# mp_rollerball.net
KiCad netlist of a schematic drawn in EAGLE
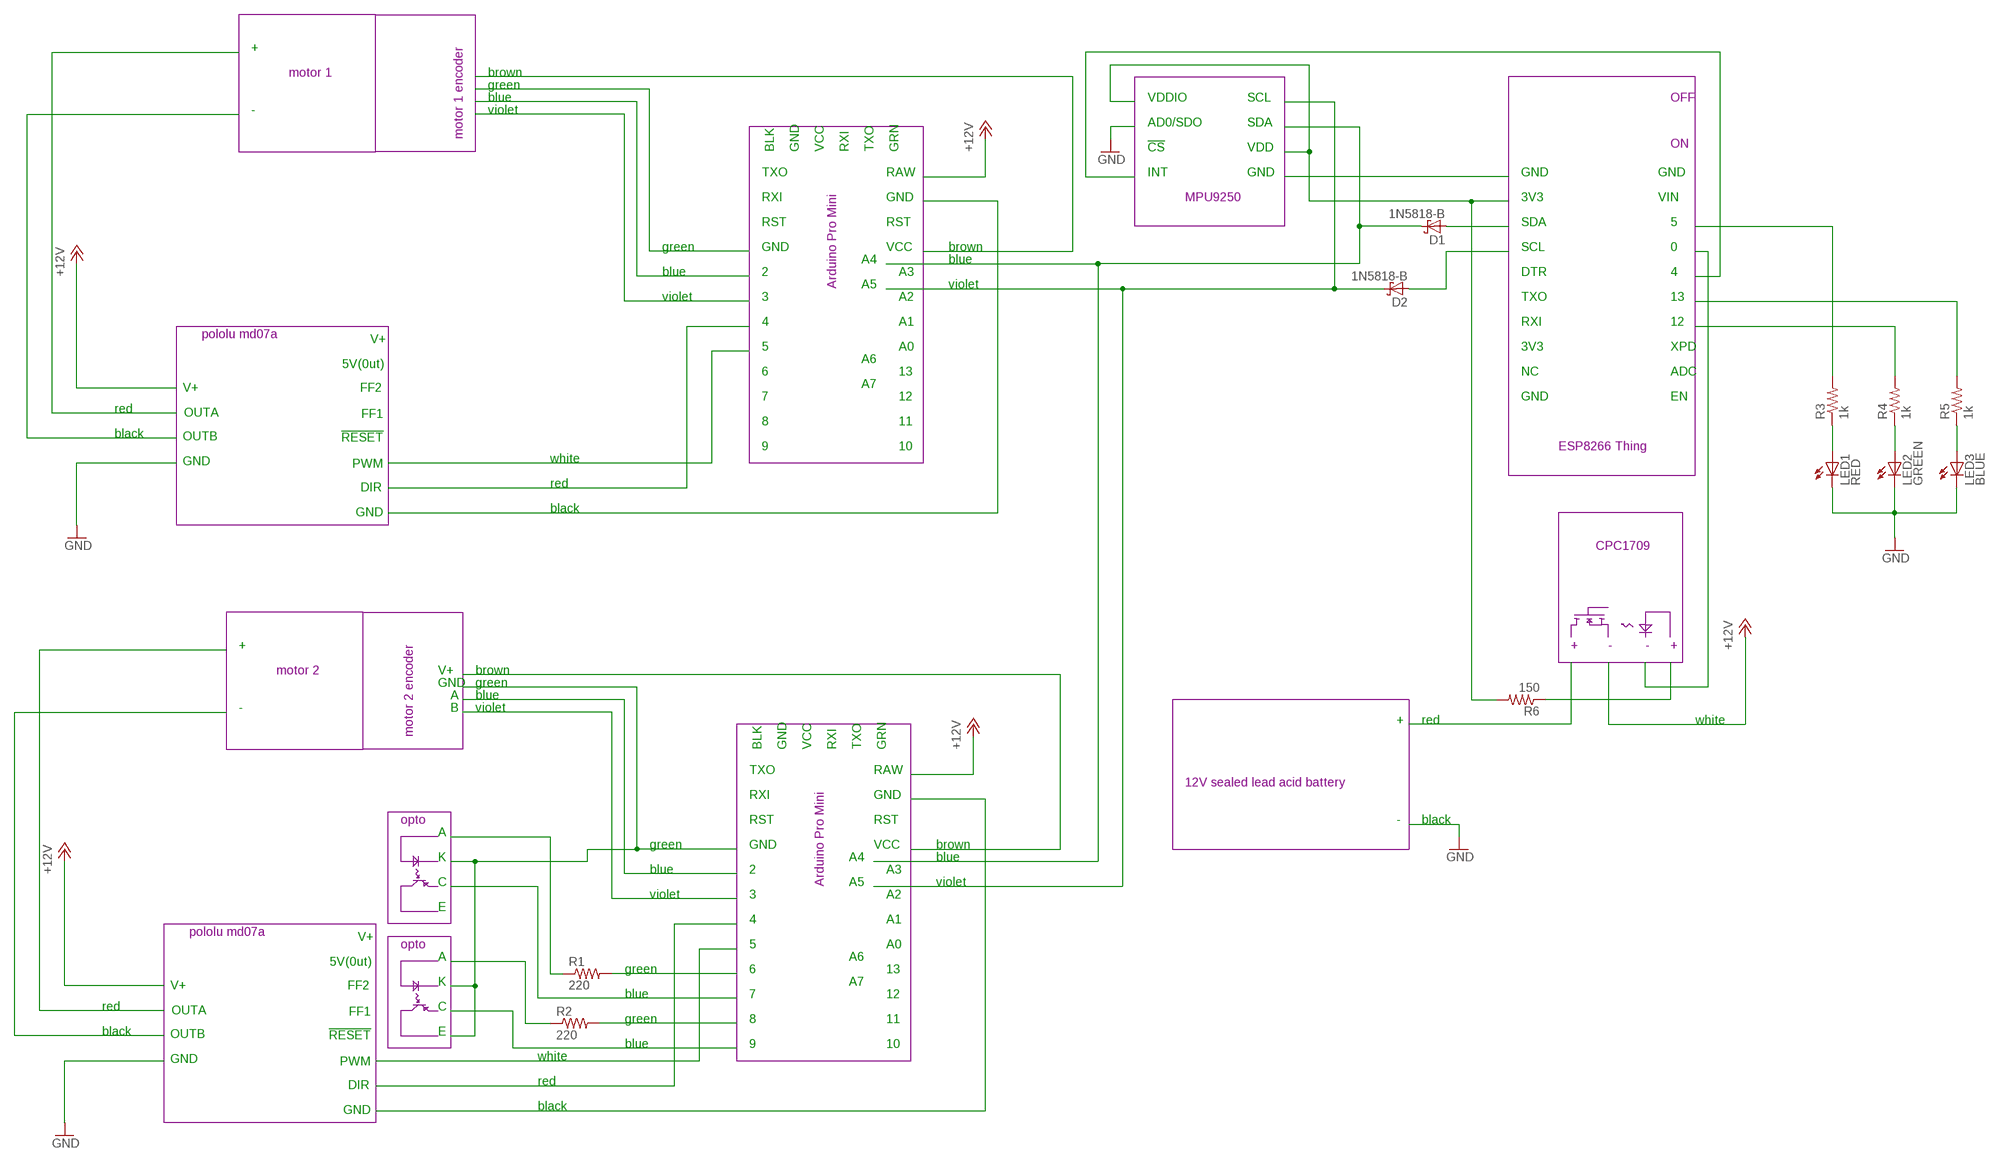
[diagram p0: schematic, sheet 1]

(export (version "E")
  (design (tool "Eeschema 10.0.6"))
  (components
    (comp (ref "D1")
      (value "1N5818-B")
      (footprint "eagle-import:DO41-7.6")
      (libsource (lib "eagle-import") (part "1N5818-B"))
    )
    (comp (ref "D2")
      (value "1N5818-B")
      (footprint "eagle-import:DO41-7.6")
      (libsource (lib "eagle-import") (part "1N5818-B"))
    )
    (comp (ref "LED1")
      (value "RED")
      (footprint "eagle-import:LED5MM")
      (libsource (lib "eagle-import") (part "LED5MM"))
    )
    (comp (ref "LED2")
      (value "GREEN")
      (footprint "eagle-import:LED5MM")
      (libsource (lib "eagle-import") (part "LED5MM"))
    )
    (comp (ref "LED3")
      (value "BLUE")
      (footprint "eagle-import:LED5MM")
      (libsource (lib "eagle-import") (part "LED5MM"))
    )
    (comp (ref "R1")
      (value "220")
      (footprint "eagle-import:0207_10")
      (libsource (lib "eagle-import") (part "R-US_0207/10"))
    )
    (comp (ref "R2")
      (value "220")
      (footprint "eagle-import:0207_10")
      (libsource (lib "eagle-import") (part "R-US_0207/10"))
    )
    (comp (ref "R3")
      (value "1k")
      (footprint "eagle-import:0207_10")
      (libsource (lib "eagle-import") (part "R-US_0207/10"))
    )
    (comp (ref "R4")
      (value "1k")
      (footprint "eagle-import:0207_10")
      (libsource (lib "eagle-import") (part "R-US_0207/10"))
    )
    (comp (ref "R5")
      (value "1k")
      (footprint "eagle-import:0207_10")
      (libsource (lib "eagle-import") (part "R-US_0207/10"))
    )
    (comp (ref "R6")
      (value "150")
      (footprint "eagle-import:0207_10")
      (libsource (lib "eagle-import") (part "R-US_0207/10"))
    )
  )
  (nets
    (net (code "2") (name "GND") (class "Default")
      (node (ref "LED1") (pin "K") (pinfunction "C_K") (pintype "passive"))
      (node (ref "LED2") (pin "K") (pinfunction "C_K") (pintype "passive"))
      (node (ref "LED3") (pin "K") (pinfunction "C_K") (pintype "passive"))
    )
    (net (code "3") (name "Net-(LED1-PadA)") (class "Default")
      (node (ref "LED1") (pin "A") (pinfunction "A_A") (pintype "passive"))
      (node (ref "R3") (pin "1") (pinfunction "1_1") (pintype "passive"))
    )
    (net (code "4") (name "Net-(LED2-PadA)") (class "Default")
      (node (ref "LED2") (pin "A") (pinfunction "A_A") (pintype "passive"))
      (node (ref "R4") (pin "1") (pinfunction "1_1") (pintype "passive"))
    )
    (net (code "5") (name "Net-(LED3-PadA)") (class "Default")
      (node (ref "LED3") (pin "A") (pinfunction "A_A") (pintype "passive"))
      (node (ref "R5") (pin "1") (pinfunction "1_1") (pintype "passive"))
    )
    (net (code "6") (name "unconnected-(D1-PadA)") (class "Default")
      (node (ref "D1") (pin "A") (pinfunction "A_A") (pintype "passive"))
    )
    (net (code "7") (name "unconnected-(D1-PadC)") (class "Default")
      (node (ref "D1") (pin "C") (pinfunction "C_C") (pintype "passive"))
    )
    (net (code "8") (name "unconnected-(D2-PadA)") (class "Default")
      (node (ref "D2") (pin "A") (pinfunction "A_A") (pintype "passive"))
    )
    (net (code "9") (name "unconnected-(D2-PadC)") (class "Default")
      (node (ref "D2") (pin "C") (pinfunction "C_C") (pintype "passive"))
    )
    (net (code "10") (name "unconnected-(R1-Pad1)") (class "Default")
      (node (ref "R1") (pin "1") (pinfunction "1_1") (pintype "passive"))
    )
    (net (code "11") (name "unconnected-(R1-Pad2)") (class "Default")
      (node (ref "R1") (pin "2") (pinfunction "2_2") (pintype "passive"))
    )
    (net (code "12") (name "unconnected-(R2-Pad1)") (class "Default")
      (node (ref "R2") (pin "1") (pinfunction "1_1") (pintype "passive"))
    )
    (net (code "13") (name "unconnected-(R2-Pad2)") (class "Default")
      (node (ref "R2") (pin "2") (pinfunction "2_2") (pintype "passive"))
    )
    (net (code "14") (name "unconnected-(R3-Pad2)") (class "Default")
      (node (ref "R3") (pin "2") (pinfunction "2_2") (pintype "passive"))
    )
    (net (code "15") (name "unconnected-(R4-Pad2)") (class "Default")
      (node (ref "R4") (pin "2") (pinfunction "2_2") (pintype "passive"))
    )
    (net (code "16") (name "unconnected-(R5-Pad2)") (class "Default")
      (node (ref "R5") (pin "2") (pinfunction "2_2") (pintype "passive"))
    )
    (net (code "17") (name "unconnected-(R6-Pad1)") (class "Default")
      (node (ref "R6") (pin "1") (pinfunction "1_1") (pintype "passive"))
    )
    (net (code "18") (name "unconnected-(R6-Pad2)") (class "Default")
      (node (ref "R6") (pin "2") (pinfunction "2_2") (pintype "passive"))
    )
  )
)
